# i6_Dimmer.net
KiCad netlist of a schematic drawn in EAGLE
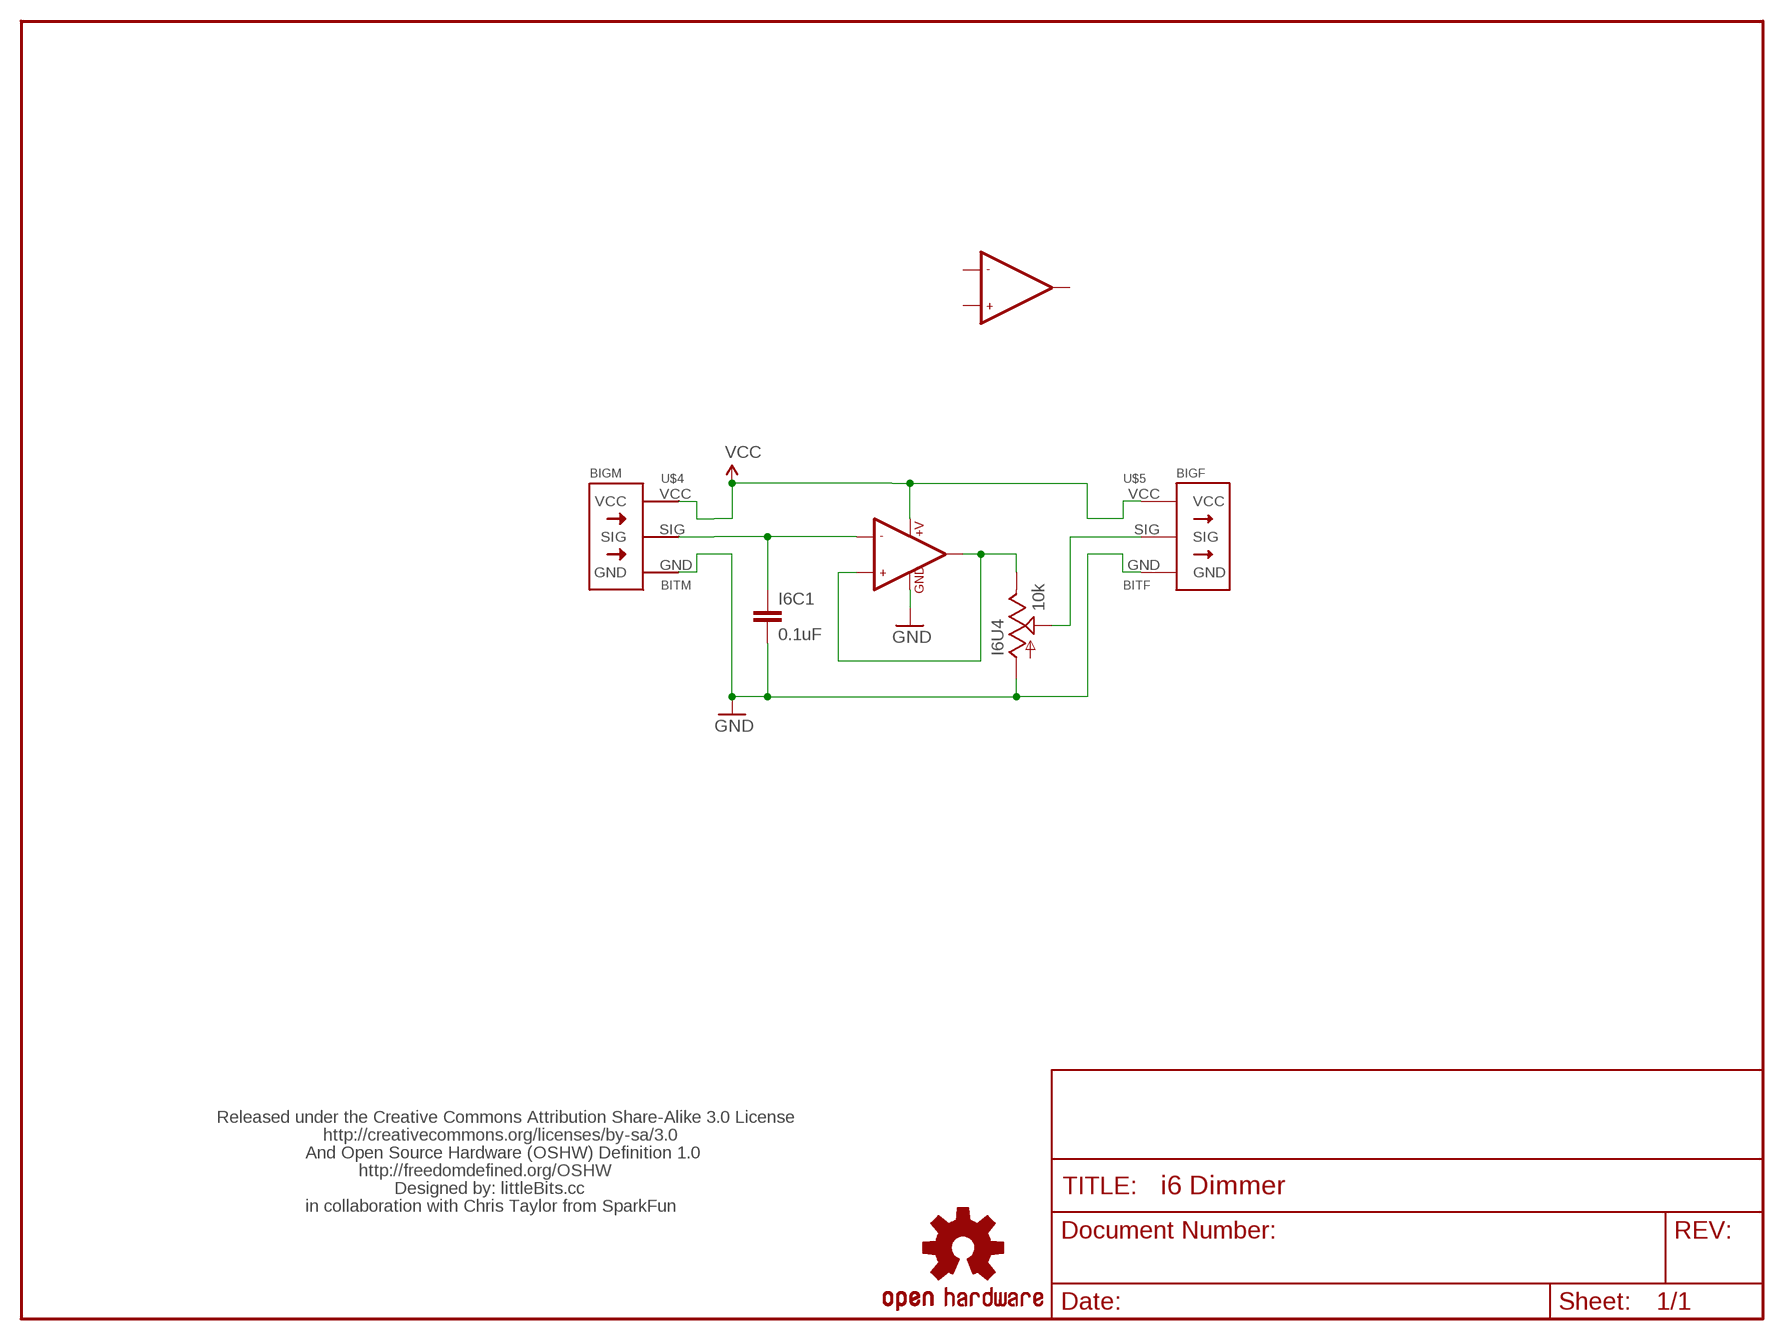
[diagram p0: schematic, sheet 1]

(export (version "E")
  (design (tool "Eeschema 10.0.6"))
  (components
    (comp (ref "I6C1")
      (value "0.1uF")
      (footprint "eagle-import:1206")
      (libsource (lib "eagle-import") (part "CAP1206"))
    )
    (comp (ref "I6U4")
      (value "10k")
      (footprint "eagle-import:ALPS_POT")
      (libsource (lib "eagle-import") (part "POT"))
    )
    (comp (ref "U$1")
      (value "LB_CREDITS")
      (footprint "eagle-import:OSHWCREDIT")
      (libsource (lib "eagle-import") (part "LB_CREDITS"))
    )
    (comp (ref "U$2")
      (value "LMV358")
      (footprint "eagle-import:SO08")
      (libsource (lib "eagle-import") (part "LMV358"))
    )
    (comp (ref "U$3")
      (value "OSHW-LOGOL")
      (footprint "eagle-import:OSHW-LOGO-L")
      (libsource (lib "eagle-import") (part "OSHW-LOGOL"))
    )
    (comp (ref "U$4")
      (value "BITM")
      (footprint "eagle-import:BITM")
      (libsource (lib "eagle-import") (part "BITM"))
    )
    (comp (ref "U$5")
      (value "BITF")
      (footprint "eagle-import:BITM")
      (libsource (lib "eagle-import") (part "BITF"))
    )
  )
  (nets
    (net (code "1") (name "GND") (class "Default")
      (node (ref "I6C1") (pin "2") (pinfunction "2_2") (pintype "passive"))
      (node (ref "I6U4") (pin "P$3") (pinfunction "A_P$3") (pintype "passive"))
      (node (ref "U$2") (pin "4") (pinfunction "GND_4") (pintype "power_in"))
      (node (ref "U$4") (pin "GND") (pinfunction "GND_GND") (pintype "bidirectional"))
      (node (ref "U$5") (pin "GND") (pinfunction "GND_GND") (pintype "bidirectional"))
    )
    (net (code "2") (name "Net-(I6U4-E)") (class "Default")
      (node (ref "I6U4") (pin "P$1") (pinfunction "E_P$1") (pintype "passive"))
      (node (ref "U$2") (pin "1") (pinfunction "OUT1_1") (pintype "output"))
      (node (ref "U$2") (pin "3") (pinfunction "+IN1_3") (pintype "input"))
    )
    (net (code "3") (name "Net-(I6U4-S)") (class "Default")
      (node (ref "I6U4") (pin "P$2") (pinfunction "S_P$2") (pintype "passive"))
      (node (ref "U$5") (pin "SIG") (pinfunction "SIG_SIG") (pintype "bidirectional"))
    )
    (net (code "4") (name "Net-(U$2A--IN1)") (class "Default")
      (node (ref "I6C1") (pin "1") (pinfunction "1_1") (pintype "passive"))
      (node (ref "U$2") (pin "2") (pinfunction "-IN1_2") (pintype "input"))
      (node (ref "U$4") (pin "SIG") (pinfunction "SIG_SIG") (pintype "bidirectional"))
    )
    (net (code "5") (name "VCC") (class "Default")
      (node (ref "U$2") (pin "8") (pinfunction "+V_8") (pintype "power_in"))
      (node (ref "U$4") (pin "VCC") (pinfunction "VCC_VCC") (pintype "bidirectional"))
      (node (ref "U$5") (pin "VCC") (pinfunction "VCC_VCC") (pintype "bidirectional"))
    )
    (net (code "6") (name "unconnected-(U$2B-+IN2-Pad5)") (class "Default")
      (node (ref "U$2") (pin "5") (pinfunction "+IN2_5") (pintype "input"))
    )
    (net (code "7") (name "unconnected-(U$2B--IN2-Pad6)") (class "Default")
      (node (ref "U$2") (pin "6") (pinfunction "-IN2_6") (pintype "input"))
    )
    (net (code "8") (name "unconnected-(U$2B-OUT2-Pad7)") (class "Default")
      (node (ref "U$2") (pin "7") (pinfunction "OUT2_7") (pintype "output"))
    )
  )
)
